# cSLIM-SA-LoRa.net
KiCad netlist of a schematic drawn in Altium Designer
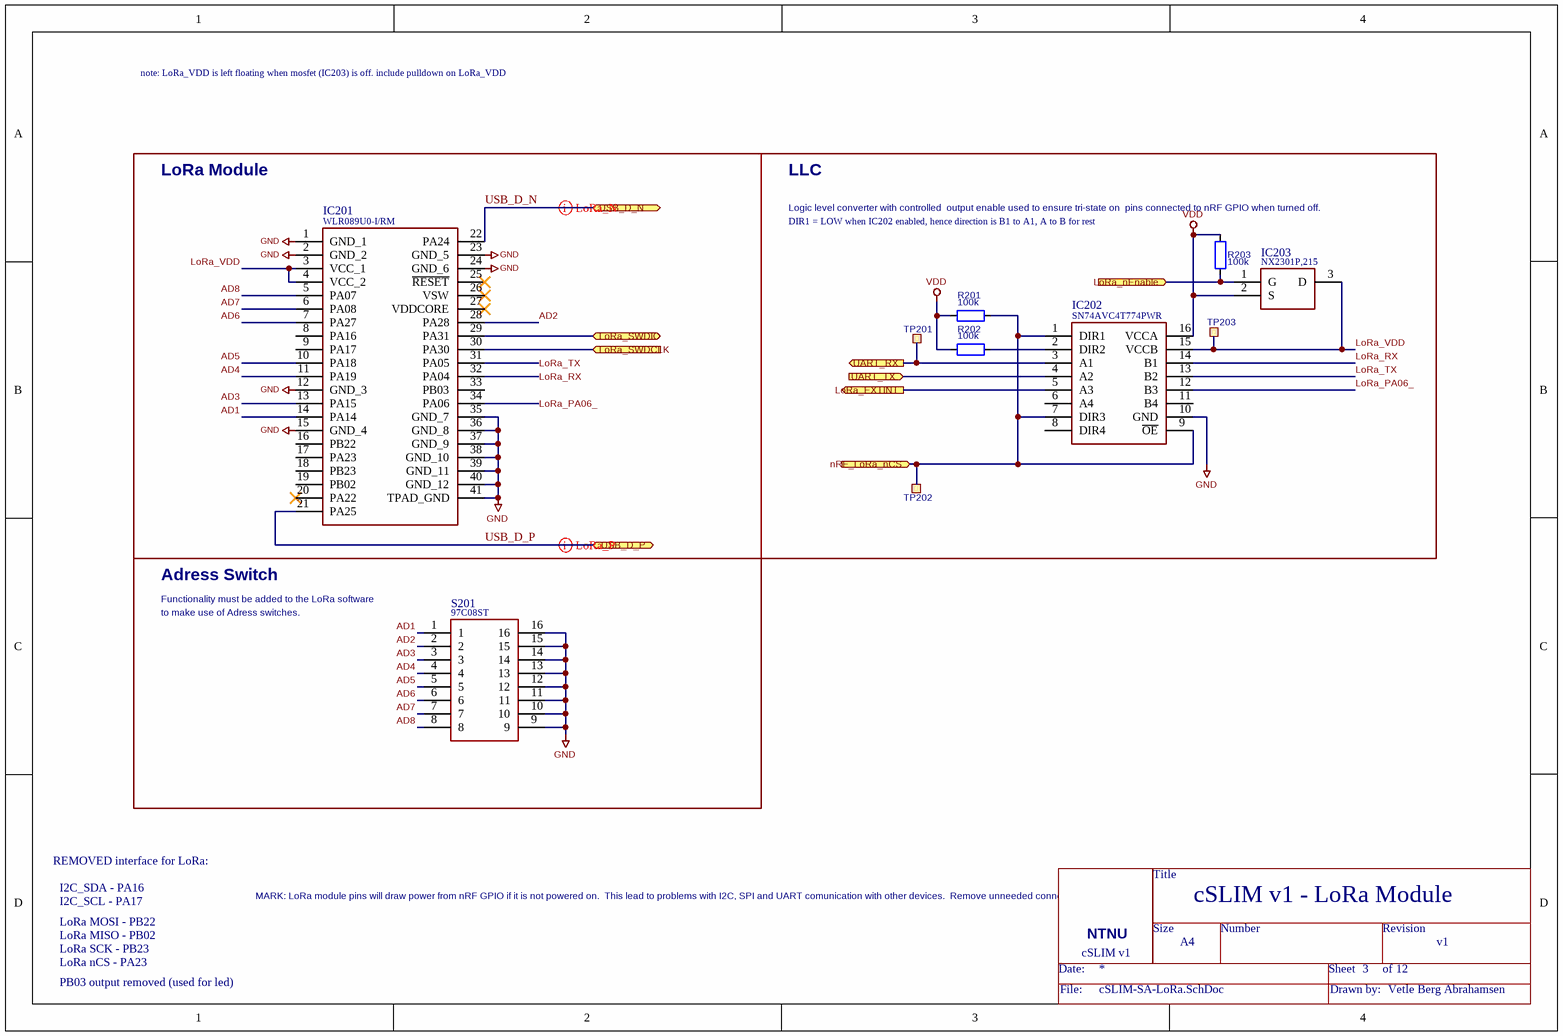
[diagram p0: cSLIM-SA-LoRa.SchDoc]

(export (version "E")
  (design (tool "Eeschema 10.0.6"))
  (components
    (comp (ref "IC201")
      (value "WLR089U0-I/RM")
      (footprint "cSLIM-SA:WLR089U0IRM")
      (description "LONG RANGE LORA MODULE (863-928")
      (fields (field (name "MOUSER PART NUMBER") "579-WLR089U0-I/RM"))
      (libsource (lib "cSLIM-SA") (part "WLR089U0-I_RM"))
    )
    (comp (ref "IC202")
      (value "SN74AVC4T774PWR")
      (footprint "cSLIM-SA:SOP65P640X120-16N")
      (description "Logic Level Converter (LLC)")
      (fields (field (name "MOUSER PART NUMBER") "595-SN74AVC4T774PWR"))
      (libsource (lib "cSLIM-SA") (part "SN74AVC4T774PWR"))
    )
    (comp (ref "IC203")
      (value "NX2301P,215")
      (footprint "cSLIM-SA:SOT95P230X110-3N")
      (description "P-Channel 20V 2A (Ta) 400mW (Ta), 2.8W (Tc) Surface Mount TO-236AB")
      (fields (field (name "MOUSER PART NUMBER") "771-NX2301P215"))
      (libsource (lib "cSLIM-SA") (part "NX2301P,215"))
    )
    (comp (ref "R201")
      (value "100k")
      (footprint "cSLIM-SA:RESC1608X55N")
      (fields (field (name "MANUFACTURER_PART_NUMBER") "RC0603FR-07100KL"))
      (libsource (lib "cSLIM-SA") (part "R"))
    )
    (comp (ref "R202")
      (value "100k")
      (footprint "cSLIM-SA:RESC1608X55N")
      (fields (field (name "MANUFACTURER_PART_NUMBER") "RC0603FR-07100KL"))
      (libsource (lib "cSLIM-SA") (part "R"))
    )
    (comp (ref "R203")
      (value "100k")
      (footprint "cSLIM-SA:RESC1608X55N")
      (fields (field (name "MANUFACTURER_PART_NUMBER") "RC0603FR-07100KL"))
      (libsource (lib "") (part "R_1"))
    )
    (comp (ref "S201")
      (value "97C08ST")
      (footprint "cSLIM-SA:SOIC127P671X170-16N")
      (description "8-Pin address switch")
      (fields (field (name "MOUSER PART NUMBER") "706-97C08ST"))
      (libsource (lib "cSLIM-SA") (part "97C08ST"))
    )
    (comp (ref "TP201")
      (value "TP")
      (footprint "cSLIM-SA:TP_SMD_Ø1.0mm")
      (description "Test points")
      (libsource (lib "") (part "TP_1"))
    )
    (comp (ref "TP202")
      (value "TP")
      (footprint "cSLIM-SA:TP_SMD_Ø1.0mm")
      (description "Test points")
      (libsource (lib "cSLIM-SA") (part "TP"))
    )
    (comp (ref "TP203")
      (value "TP")
      (footprint "cSLIM-SA:TP_SMD_Ø1.0mm")
      (description "Test points")
      (libsource (lib "") (part "TP_1"))
    )
  )
  (nets
    (net (code "1") (name "/AD1") (class "Default")
      (node (ref "IC201") (pin "14") (pinfunction "PA14_14") (pintype "passive"))
      (node (ref "S201") (pin "1") (pinfunction "1_1") (pintype "passive"))
    )
    (net (code "2") (name "/AD2") (class "Default")
      (node (ref "IC201") (pin "28") (pinfunction "PA28_28") (pintype "passive"))
      (node (ref "S201") (pin "2") (pinfunction "2_2") (pintype "passive"))
    )
    (net (code "3") (name "/AD3") (class "Default")
      (node (ref "IC201") (pin "13") (pinfunction "PA15_13") (pintype "passive"))
      (node (ref "S201") (pin "3") (pinfunction "3_3") (pintype "passive"))
    )
    (net (code "4") (name "/AD4") (class "Default")
      (node (ref "IC201") (pin "11") (pinfunction "PA19_11") (pintype "passive"))
      (node (ref "S201") (pin "4") (pinfunction "4_4") (pintype "passive"))
    )
    (net (code "5") (name "/AD5") (class "Default")
      (node (ref "IC201") (pin "10") (pinfunction "PA18_10") (pintype "passive"))
      (node (ref "S201") (pin "5") (pinfunction "5_5") (pintype "passive"))
    )
    (net (code "6") (name "/AD6") (class "Default")
      (node (ref "IC201") (pin "7") (pinfunction "PA27_7") (pintype "passive"))
      (node (ref "S201") (pin "6") (pinfunction "6_6") (pintype "passive"))
    )
    (net (code "7") (name "/AD7") (class "Default")
      (node (ref "IC201") (pin "6") (pinfunction "PA08_6") (pintype "passive"))
      (node (ref "S201") (pin "7") (pinfunction "7_7") (pintype "passive"))
    )
    (net (code "8") (name "/AD8") (class "Default")
      (node (ref "IC201") (pin "5") (pinfunction "PA07_5") (pintype "passive"))
      (node (ref "S201") (pin "8") (pinfunction "8_8") (pintype "passive"))
    )
    (net (code "9") (name "/LoRa_EXTINT") (class "Default")
      (node (ref "IC202") (pin "5") (pinfunction "A3_5") (pintype "passive"))
    )
    (net (code "10") (name "/LoRa_PA06_") (class "Default")
      (node (ref "IC201") (pin "34") (pinfunction "PA06_34") (pintype "passive"))
      (node (ref "IC202") (pin "12") (pinfunction "B3_12") (pintype "passive"))
    )
    (net (code "11") (name "/LoRa_RX") (class "Default")
      (node (ref "IC201") (pin "32") (pinfunction "PA04_32") (pintype "passive"))
      (node (ref "IC202") (pin "14") (pinfunction "B1_14") (pintype "passive"))
    )
    (net (code "12") (name "/LoRa_SWDCLK") (class "Default")
      (node (ref "IC201") (pin "30") (pinfunction "PA30_30") (pintype "passive"))
    )
    (net (code "13") (name "/LoRa_SWDIO") (class "Default")
      (node (ref "IC201") (pin "29") (pinfunction "PA31_29") (pintype "passive"))
    )
    (net (code "14") (name "/LoRa_TX") (class "Default")
      (node (ref "IC201") (pin "31") (pinfunction "PA05_31") (pintype "passive"))
      (node (ref "IC202") (pin "13") (pinfunction "B2_13") (pintype "passive"))
    )
    (net (code "15") (name "/LoRa_VDD") (class "Default")
      (node (ref "IC201") (pin "3") (pinfunction "VCC_1_3") (pintype "passive"))
      (node (ref "IC201") (pin "4") (pinfunction "VCC_2_4") (pintype "passive"))
      (node (ref "IC202") (pin "15") (pinfunction "VCCB_15") (pintype "passive"))
      (node (ref "IC203") (pin "3") (pinfunction "D_3") (pintype "passive"))
      (node (ref "TP203") (pin "1") (pinfunction "1_1") (pintype "passive"))
    )
    (net (code "16") (name "/LoRa_nEnable") (class "Default")
      (node (ref "IC203") (pin "1") (pinfunction "G_1") (pintype "passive"))
      (node (ref "R203") (pin "1") (pinfunction "1_1") (pintype "passive"))
    )
    (net (code "17") (name "/UART_RX") (class "Default")
      (node (ref "IC202") (pin "3") (pinfunction "A1_3") (pintype "passive"))
      (node (ref "TP201") (pin "1") (pinfunction "1_1") (pintype "passive"))
    )
    (net (code "18") (name "/UART_TX") (class "Default")
      (node (ref "IC202") (pin "4") (pinfunction "A2_4") (pintype "passive"))
    )
    (net (code "19") (name "/USB_D_N") (class "Default")
      (node (ref "IC201") (pin "22") (pinfunction "PA24_22") (pintype "passive"))
    )
    (net (code "20") (name "/USB_D_P") (class "Default")
      (node (ref "IC201") (pin "21") (pinfunction "PA25_21") (pintype "passive"))
    )
    (net (code "21") (name "/nRF_LoRa_nCS") (class "Default")
      (node (ref "IC202") (pin "1") (pinfunction "DIR1_1") (pintype "passive"))
      (node (ref "IC202") (pin "7") (pinfunction "DIR3_7") (pintype "passive"))
      (node (ref "IC202") (pin "9") (pinfunction "~{OE}_9") (pintype "passive"))
      (node (ref "R201") (pin "1") (pinfunction "1_1") (pintype "passive"))
      (node (ref "TP202") (pin "1") (pinfunction "1_1") (pintype "passive"))
    )
    (net (code "22") (name "GND") (class "Default")
      (node (ref "IC201") (pin "1") (pinfunction "GND_1_1") (pintype "passive"))
      (node (ref "IC201") (pin "12") (pinfunction "GND_3_12") (pintype "passive"))
      (node (ref "IC201") (pin "15") (pinfunction "GND_4_15") (pintype "passive"))
      (node (ref "IC201") (pin "2") (pinfunction "GND_2_2") (pintype "passive"))
      (node (ref "IC201") (pin "23") (pinfunction "GND_5_23") (pintype "passive"))
      (node (ref "IC201") (pin "24") (pinfunction "GND_6_24") (pintype "passive"))
      (node (ref "IC201") (pin "35") (pinfunction "GND_7_35") (pintype "passive"))
      (node (ref "IC201") (pin "36") (pinfunction "GND_8_36") (pintype "passive"))
      (node (ref "IC201") (pin "37") (pinfunction "GND_9_37") (pintype "passive"))
      (node (ref "IC201") (pin "38") (pinfunction "GND_10_38") (pintype "passive"))
      (node (ref "IC201") (pin "39") (pinfunction "GND_11_39") (pintype "passive"))
      (node (ref "IC201") (pin "40") (pinfunction "GND_12_40") (pintype "passive"))
      (node (ref "IC201") (pin "41") (pinfunction "TPAD_GND_41") (pintype "passive"))
      (node (ref "IC202") (pin "10") (pinfunction "GND_10") (pintype "passive"))
      (node (ref "S201") (pin "10") (pinfunction "10_10") (pintype "passive"))
      (node (ref "S201") (pin "11") (pinfunction "11_11") (pintype "passive"))
      (node (ref "S201") (pin "12") (pinfunction "12_12") (pintype "passive"))
      (node (ref "S201") (pin "13") (pinfunction "13_13") (pintype "passive"))
      (node (ref "S201") (pin "14") (pinfunction "14_14") (pintype "passive"))
      (node (ref "S201") (pin "15") (pinfunction "15_15") (pintype "passive"))
      (node (ref "S201") (pin "16") (pinfunction "16_16") (pintype "passive"))
      (node (ref "S201") (pin "9") (pinfunction "9_9") (pintype "passive"))
    )
    (net (code "23") (name "Net-(IC202-DIR2)") (class "Default")
      (node (ref "IC202") (pin "2") (pinfunction "DIR2_2") (pintype "passive"))
      (node (ref "R202") (pin "1") (pinfunction "1_1") (pintype "passive"))
    )
    (net (code "24") (name "VDD") (class "Default")
      (node (ref "IC202") (pin "16") (pinfunction "VCCA_16") (pintype "passive"))
      (node (ref "IC203") (pin "2") (pinfunction "S_2") (pintype "passive"))
      (node (ref "R201") (pin "2") (pinfunction "2_2") (pintype "passive"))
      (node (ref "R202") (pin "2") (pinfunction "2_2") (pintype "passive"))
      (node (ref "R203") (pin "2") (pinfunction "2_2") (pintype "passive"))
    )
    (net (code "25") (name "unconnected-(IC201-PA16-Pad8)") (class "Default")
      (node (ref "IC201") (pin "8") (pinfunction "PA16_8") (pintype "passive"))
    )
    (net (code "26") (name "unconnected-(IC201-PA17-Pad9)") (class "Default")
      (node (ref "IC201") (pin "9") (pinfunction "PA17_9") (pintype "passive"))
    )
    (net (code "27") (name "unconnected-(IC201-PA22-Pad20)") (class "Default")
      (node (ref "IC201") (pin "20") (pinfunction "PA22_20") (pintype "passive+no_connect"))
    )
    (net (code "28") (name "unconnected-(IC201-PA23-Pad17)") (class "Default")
      (node (ref "IC201") (pin "17") (pinfunction "PA23_17") (pintype "passive"))
    )
    (net (code "29") (name "unconnected-(IC201-PB02-Pad19)") (class "Default")
      (node (ref "IC201") (pin "19") (pinfunction "PB02_19") (pintype "passive"))
    )
    (net (code "30") (name "unconnected-(IC201-PB03-Pad33)") (class "Default")
      (node (ref "IC201") (pin "33") (pinfunction "PB03_33") (pintype "passive"))
    )
    (net (code "31") (name "unconnected-(IC201-PB22-Pad16)") (class "Default")
      (node (ref "IC201") (pin "16") (pinfunction "PB22_16") (pintype "passive"))
    )
    (net (code "32") (name "unconnected-(IC201-PB23-Pad18)") (class "Default")
      (node (ref "IC201") (pin "18") (pinfunction "PB23_18") (pintype "passive"))
    )
    (net (code "33") (name "unconnected-(IC201-VDDCORE-Pad27)") (class "Default")
      (node (ref "IC201") (pin "27") (pinfunction "VDDCORE_27") (pintype "passive+no_connect"))
    )
    (net (code "34") (name "unconnected-(IC201-VSW-Pad26)") (class "Default")
      (node (ref "IC201") (pin "26") (pinfunction "VSW_26") (pintype "passive+no_connect"))
    )
    (net (code "35") (name "unconnected-(IC201-~{RESET}-Pad25)") (class "Default")
      (node (ref "IC201") (pin "25") (pinfunction "~{RESET}_25") (pintype "passive+no_connect"))
    )
    (net (code "36") (name "unconnected-(IC202-A4-Pad6)") (class "Default")
      (node (ref "IC202") (pin "6") (pinfunction "A4_6") (pintype "passive"))
    )
    (net (code "37") (name "unconnected-(IC202-B4-Pad11)") (class "Default")
      (node (ref "IC202") (pin "11") (pinfunction "B4_11") (pintype "passive"))
    )
    (net (code "38") (name "unconnected-(IC202-DIR4-Pad8)") (class "Default")
      (node (ref "IC202") (pin "8") (pinfunction "DIR4_8") (pintype "passive"))
    )
  )
)
